# M220pal.net
KiCad netlist of a schematic drawn in EAGLE
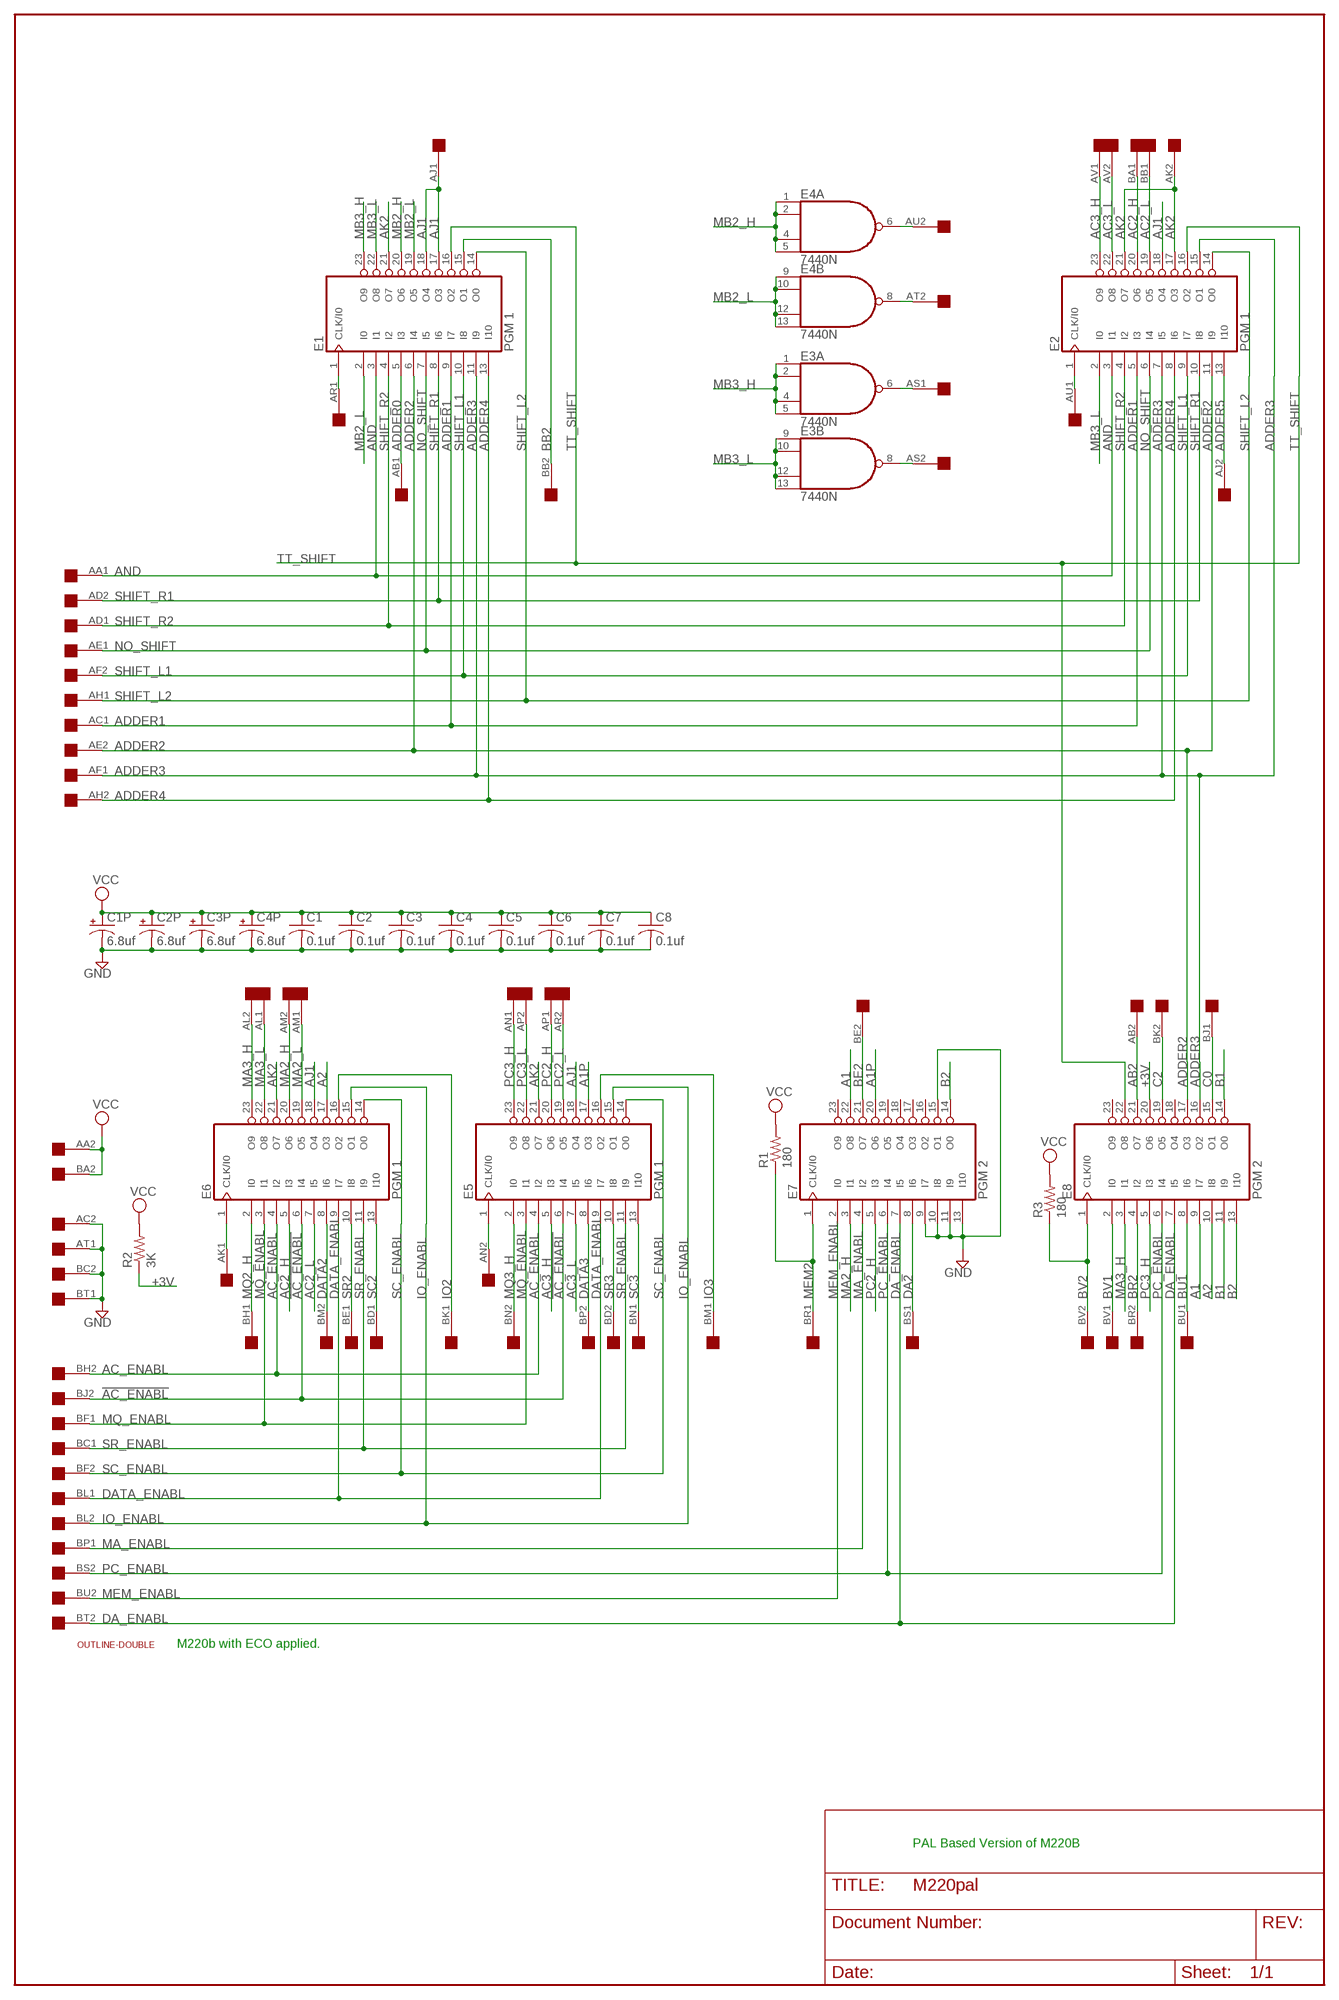
[diagram p0: schematic, sheet 1]

(export (version "E")
  (design (tool "Eeschema 10.0.6"))
  (components
    (comp (ref "C1")
      (value "0.1uf")
      (footprint "eagle-import:C050-025X075")
      (libsource (lib "eagle-import") (part "C-US050-025X075"))
    )
    (comp (ref "C1P")
      (value "6.8uf")
      (footprint "eagle-import:E15-5")
      (libsource (lib "eagle-import") (part "CPOL-USE15-5AXIAL"))
    )
    (comp (ref "C2")
      (value "0.1uf")
      (footprint "eagle-import:C050-025X075")
      (libsource (lib "eagle-import") (part "C-US050-025X075"))
    )
    (comp (ref "C2P")
      (value "6.8uf")
      (footprint "eagle-import:E15-5")
      (libsource (lib "eagle-import") (part "CPOL-USE15-5AXIAL"))
    )
    (comp (ref "C3")
      (value "0.1uf")
      (footprint "eagle-import:C050-025X075")
      (libsource (lib "eagle-import") (part "C-US050-025X075"))
    )
    (comp (ref "C3P")
      (value "6.8uf")
      (footprint "eagle-import:E15-5")
      (libsource (lib "eagle-import") (part "CPOL-USE15-5AXIAL"))
    )
    (comp (ref "C4")
      (value "0.1uf")
      (footprint "eagle-import:C050-025X075")
      (libsource (lib "eagle-import") (part "C-US050-025X075"))
    )
    (comp (ref "C4P")
      (value "6.8uf")
      (footprint "eagle-import:E15-5")
      (libsource (lib "eagle-import") (part "CPOL-USE15-5AXIAL"))
    )
    (comp (ref "C5")
      (value "0.1uf")
      (footprint "eagle-import:C050-025X075")
      (libsource (lib "eagle-import") (part "C-US050-025X075"))
    )
    (comp (ref "C6")
      (value "0.1uf")
      (footprint "eagle-import:C050-025X075")
      (libsource (lib "eagle-import") (part "C-US050-025X075"))
    )
    (comp (ref "C7")
      (value "0.1uf")
      (footprint "eagle-import:C050-025X075")
      (libsource (lib "eagle-import") (part "C-US050-025X075"))
    )
    (comp (ref "C8")
      (value "0.1uf")
      (footprint "eagle-import:C050-025X075")
      (libsource (lib "eagle-import") (part "C-US050-025X075"))
    )
    (comp (ref "E1")
      (value "PGM 1")
      (footprint "eagle-import:DIL24-3")
      (fields (field (name "MPN") "GAL22V10D-7LPN"))
      (libsource (lib "eagle-import") (part "22V10"))
    )
    (comp (ref "E2")
      (value "PGM 1")
      (footprint "eagle-import:DIL24-3")
      (fields (field (name "MPN") "GAL22V10D-7LPN"))
      (libsource (lib "eagle-import") (part "22V10"))
    )
    (comp (ref "E3")
      (value "7440N")
      (footprint "eagle-import:DIL14")
      (libsource (lib "eagle-import") (part "7420NS"))
    )
    (comp (ref "E4")
      (value "7440N")
      (footprint "eagle-import:DIL14")
      (libsource (lib "eagle-import") (part "7420NS"))
    )
    (comp (ref "E5")
      (value "PGM 1")
      (footprint "eagle-import:DIL24-3")
      (fields (field (name "MPN") "GAL22V10D-7LPN"))
      (libsource (lib "eagle-import") (part "22V10"))
    )
    (comp (ref "E6")
      (value "PGM 1")
      (footprint "eagle-import:DIL24-3")
      (fields (field (name "MPN") "GAL22V10D-7LPN"))
      (libsource (lib "eagle-import") (part "22V10"))
    )
    (comp (ref "E7")
      (value "PGM 2")
      (footprint "eagle-import:DIL24-3")
      (fields (field (name "MPN") "GAL22V10D-7LPN"))
      (libsource (lib "eagle-import") (part "22V10"))
    )
    (comp (ref "E8")
      (value "PGM 2")
      (footprint "eagle-import:DIL24-3")
      (fields (field (name "MPN") "GAL22V10D-7LPN"))
      (libsource (lib "eagle-import") (part "22V10"))
    )
    (comp (ref "R1")
      (value "180")
      (footprint "eagle-import:0207_10")
      (libsource (lib "eagle-import") (part "R-US_0207/10"))
    )
    (comp (ref "R2")
      (value "3K")
      (footprint "eagle-import:0207_10")
      (libsource (lib "eagle-import") (part "R-US_0207/10"))
    )
    (comp (ref "R3")
      (value "180")
      (footprint "eagle-import:0207_10")
      (libsource (lib "eagle-import") (part "R-US_0207/10"))
    )
    (comp (ref "U$1")
      (value "DOUBLE")
      (footprint "eagle-import:EDGE-CON4")
      (libsource (lib "eagle-import") (part "DOUBLE"))
    )
    (comp (ref "U$2")
      (value "OUTLINE-DOUBLE")
      (footprint "eagle-import:DOUBLE")
      (libsource (lib "eagle-import") (part "OUTLINE-DOUBLE"))
    )
  )
  (nets
    (net (code "1") (name "/+3V") (class "Default")
      (node (ref "E8") (pin "20") (pinfunction "O6_20") (pintype "bidirectional"))
      (node (ref "R2") (pin "1") (pinfunction "1_1") (pintype "passive"))
    )
    (net (code "2") (name "/A1") (class "Default")
      (node (ref "E7") (pin "22") (pinfunction "O8_22") (pintype "bidirectional"))
      (node (ref "E8") (pin "9") (pinfunction "I7_9") (pintype "input"))
    )
    (net (code "3") (name "/A1P") (class "Default")
      (node (ref "E5") (pin "17") (pinfunction "O3_17") (pintype "bidirectional"))
      (node (ref "E7") (pin "20") (pinfunction "O6_20") (pintype "bidirectional"))
    )
    (net (code "4") (name "/A2") (class "Default")
      (node (ref "E6") (pin "17") (pinfunction "O3_17") (pintype "bidirectional"))
      (node (ref "E8") (pin "10") (pinfunction "I8_10") (pintype "input"))
    )
    (net (code "5") (name "/AB2") (class "Default")
      (node (ref "E8") (pin "21") (pinfunction "O7_21") (pintype "bidirectional"))
      (node (ref "U$1") (pin "AB2") (pinfunction "1_AB2") (pintype "bidirectional"))
    )
    (net (code "6") (name "/AC2_H") (class "Default")
      (node (ref "E2") (pin "20") (pinfunction "O6_20") (pintype "bidirectional"))
      (node (ref "E6") (pin "5") (pinfunction "I3_5") (pintype "input"))
      (node (ref "U$1") (pin "BA1") (pinfunction "1_BA1") (pintype "bidirectional"))
    )
    (net (code "7") (name "/AC2_L") (class "Default")
      (node (ref "E2") (pin "19") (pinfunction "O5_19") (pintype "bidirectional"))
      (node (ref "E6") (pin "7") (pinfunction "I5_7") (pintype "input"))
      (node (ref "U$1") (pin "BB1") (pinfunction "1_BB1") (pintype "bidirectional"))
    )
    (net (code "8") (name "/AC3_H") (class "Default")
      (node (ref "E2") (pin "23") (pinfunction "O9_23") (pintype "bidirectional"))
      (node (ref "E5") (pin "5") (pinfunction "I3_5") (pintype "input"))
      (node (ref "U$1") (pin "AV1") (pinfunction "1_AV1") (pintype "bidirectional"))
    )
    (net (code "9") (name "/AC3_L") (class "Default")
      (node (ref "E2") (pin "22") (pinfunction "O8_22") (pintype "bidirectional"))
      (node (ref "E5") (pin "7") (pinfunction "I5_7") (pintype "input"))
      (node (ref "U$1") (pin "AV2") (pinfunction "1_AV2") (pintype "bidirectional"))
    )
    (net (code "10") (name "/AC_ENABL") (class "Default")
      (node (ref "E5") (pin "4") (pinfunction "I2_4") (pintype "input"))
      (node (ref "E6") (pin "4") (pinfunction "I2_4") (pintype "input"))
      (node (ref "U$1") (pin "BH2") (pinfunction "1_BH2") (pintype "bidirectional"))
    )
    (net (code "11") (name "/ADDER0") (class "Default")
      (node (ref "E1") (pin "5") (pinfunction "I3_5") (pintype "input"))
      (node (ref "U$1") (pin "AB1") (pinfunction "1_AB1") (pintype "bidirectional"))
    )
    (net (code "12") (name "/ADDER1") (class "Default")
      (node (ref "E1") (pin "9") (pinfunction "I7_9") (pintype "input"))
      (node (ref "E2") (pin "5") (pinfunction "I3_5") (pintype "input"))
      (node (ref "U$1") (pin "AC1") (pinfunction "1_AC1") (pintype "bidirectional"))
    )
    (net (code "13") (name "/ADDER2") (class "Default")
      (node (ref "E1") (pin "6") (pinfunction "I4_6") (pintype "input"))
      (node (ref "E2") (pin "11") (pinfunction "I9_11") (pintype "input"))
      (node (ref "E8") (pin "17") (pinfunction "O3_17") (pintype "bidirectional"))
      (node (ref "U$1") (pin "AE2") (pinfunction "1_AE2") (pintype "bidirectional"))
    )
    (net (code "14") (name "/ADDER3") (class "Default")
      (node (ref "E1") (pin "11") (pinfunction "I9_11") (pintype "input"))
      (node (ref "E2") (pin "15") (pinfunction "O1_15") (pintype "bidirectional"))
      (node (ref "E2") (pin "7") (pinfunction "I5_7") (pintype "input"))
      (node (ref "E8") (pin "16") (pinfunction "O2_16") (pintype "bidirectional"))
      (node (ref "U$1") (pin "AF1") (pinfunction "1_AF1") (pintype "bidirectional"))
    )
    (net (code "15") (name "/ADDER4") (class "Default")
      (node (ref "E1") (pin "13") (pinfunction "I10_13") (pintype "input"))
      (node (ref "E2") (pin "8") (pinfunction "I6_8") (pintype "input"))
      (node (ref "U$1") (pin "AH2") (pinfunction "1_AH2") (pintype "bidirectional"))
    )
    (net (code "16") (name "/ADDER5") (class "Default")
      (node (ref "E2") (pin "13") (pinfunction "I10_13") (pintype "input"))
      (node (ref "U$1") (pin "AJ2") (pinfunction "1_AJ2") (pintype "bidirectional"))
    )
    (net (code "17") (name "/AJ1") (class "Default")
      (node (ref "E1") (pin "17") (pinfunction "O3_17") (pintype "bidirectional"))
      (node (ref "E1") (pin "18") (pinfunction "O4_18") (pintype "bidirectional"))
      (node (ref "E2") (pin "18") (pinfunction "O4_18") (pintype "bidirectional"))
      (node (ref "E5") (pin "18") (pinfunction "O4_18") (pintype "bidirectional"))
      (node (ref "E6") (pin "18") (pinfunction "O4_18") (pintype "bidirectional"))
      (node (ref "U$1") (pin "AJ1") (pinfunction "1_AJ1") (pintype "bidirectional"))
    )
    (net (code "18") (name "/AK2") (class "Default")
      (node (ref "E1") (pin "21") (pinfunction "O7_21") (pintype "bidirectional"))
      (node (ref "E2") (pin "17") (pinfunction "O3_17") (pintype "bidirectional"))
      (node (ref "E2") (pin "21") (pinfunction "O7_21") (pintype "bidirectional"))
      (node (ref "E5") (pin "21") (pinfunction "O7_21") (pintype "bidirectional"))
      (node (ref "E6") (pin "21") (pinfunction "O7_21") (pintype "bidirectional"))
      (node (ref "U$1") (pin "AK2") (pinfunction "1_AK2") (pintype "bidirectional"))
    )
    (net (code "19") (name "/AND") (class "Default")
      (node (ref "E1") (pin "3") (pinfunction "I1_3") (pintype "input"))
      (node (ref "E2") (pin "3") (pinfunction "I1_3") (pintype "input"))
      (node (ref "U$1") (pin "AA1") (pinfunction "1_AA1") (pintype "bidirectional"))
    )
    (net (code "20") (name "/B1") (class "Default")
      (node (ref "E8") (pin "11") (pinfunction "I9_11") (pintype "input"))
      (node (ref "E8") (pin "14") (pinfunction "O0_14") (pintype "bidirectional"))
    )
    (net (code "21") (name "/B2") (class "Default")
      (node (ref "E7") (pin "14") (pinfunction "O0_14") (pintype "bidirectional"))
      (node (ref "E8") (pin "13") (pinfunction "I10_13") (pintype "input"))
    )
    (net (code "22") (name "/BB2") (class "Default")
      (node (ref "E1") (pin "15") (pinfunction "O1_15") (pintype "bidirectional"))
      (node (ref "U$1") (pin "BB2") (pinfunction "1_BB2") (pintype "bidirectional"))
    )
    (net (code "23") (name "/BE2") (class "Default")
      (node (ref "E7") (pin "21") (pinfunction "O7_21") (pintype "bidirectional"))
      (node (ref "U$1") (pin "BE2") (pinfunction "1_BE2") (pintype "bidirectional"))
    )
    (net (code "24") (name "/BR2") (class "Default")
      (node (ref "E8") (pin "4") (pinfunction "I2_4") (pintype "input"))
      (node (ref "U$1") (pin "BR2") (pinfunction "1_BR2") (pintype "bidirectional"))
    )
    (net (code "25") (name "/BU1") (class "Default")
      (node (ref "E8") (pin "8") (pinfunction "I6_8") (pintype "input"))
      (node (ref "U$1") (pin "BU1") (pinfunction "1_BU1") (pintype "bidirectional"))
    )
    (net (code "26") (name "/BV1") (class "Default")
      (node (ref "E8") (pin "2") (pinfunction "I0_2") (pintype "input"))
      (node (ref "U$1") (pin "BV1") (pinfunction "1_BV1") (pintype "bidirectional"))
    )
    (net (code "27") (name "/BV2") (class "Default")
      (node (ref "E8") (pin "1") (pinfunction "CLK/I0_1") (pintype "input"))
      (node (ref "R3") (pin "1") (pinfunction "1_1") (pintype "passive"))
      (node (ref "U$1") (pin "BV2") (pinfunction "1_BV2") (pintype "bidirectional"))
    )
    (net (code "28") (name "/C0") (class "Default")
      (node (ref "E8") (pin "15") (pinfunction "O1_15") (pintype "bidirectional"))
      (node (ref "U$1") (pin "BJ1") (pinfunction "1_BJ1") (pintype "bidirectional"))
    )
    (net (code "29") (name "/C2") (class "Default")
      (node (ref "E8") (pin "19") (pinfunction "O5_19") (pintype "bidirectional"))
      (node (ref "U$1") (pin "BK2") (pinfunction "1_BK2") (pintype "bidirectional"))
    )
    (net (code "30") (name "/DA2") (class "Default")
      (node (ref "E7") (pin "8") (pinfunction "I6_8") (pintype "input"))
      (node (ref "U$1") (pin "BS1") (pinfunction "1_BS1") (pintype "bidirectional"))
    )
    (net (code "31") (name "/DATA2") (class "Default")
      (node (ref "E6") (pin "8") (pinfunction "I6_8") (pintype "input"))
      (node (ref "U$1") (pin "BM2") (pinfunction "1_BM2") (pintype "bidirectional"))
    )
    (net (code "32") (name "/DATA3") (class "Default")
      (node (ref "E5") (pin "8") (pinfunction "I6_8") (pintype "input"))
      (node (ref "U$1") (pin "BP2") (pinfunction "1_BP2") (pintype "bidirectional"))
    )
    (net (code "33") (name "/DATA_ENABL") (class "Default")
      (node (ref "E5") (pin "9") (pinfunction "I7_9") (pintype "input"))
      (node (ref "E6") (pin "9") (pinfunction "I7_9") (pintype "input"))
      (node (ref "U$1") (pin "BL1") (pinfunction "1_BL1") (pintype "bidirectional"))
    )
    (net (code "34") (name "/DA_ENABL") (class "Default")
      (node (ref "E7") (pin "7") (pinfunction "I5_7") (pintype "input"))
      (node (ref "E8") (pin "7") (pinfunction "I5_7") (pintype "input"))
      (node (ref "U$1") (pin "BT2") (pinfunction "1_BT2") (pintype "bidirectional"))
    )
    (net (code "35") (name "/IO2") (class "Default")
      (node (ref "E6") (pin "16") (pinfunction "O2_16") (pintype "bidirectional"))
      (node (ref "U$1") (pin "BK1") (pinfunction "1_BK1") (pintype "bidirectional"))
    )
    (net (code "36") (name "/IO3") (class "Default")
      (node (ref "E5") (pin "16") (pinfunction "O2_16") (pintype "bidirectional"))
      (node (ref "U$1") (pin "BM1") (pinfunction "1_BM1") (pintype "bidirectional"))
    )
    (net (code "37") (name "/IO_ENABL") (class "Default")
      (node (ref "E5") (pin "15") (pinfunction "O1_15") (pintype "bidirectional"))
      (node (ref "E6") (pin "15") (pinfunction "O1_15") (pintype "bidirectional"))
      (node (ref "U$1") (pin "BL2") (pinfunction "1_BL2") (pintype "bidirectional"))
    )
    (net (code "38") (name "/MA2_H") (class "Default")
      (node (ref "E6") (pin "20") (pinfunction "O6_20") (pintype "bidirectional"))
      (node (ref "E7") (pin "3") (pinfunction "I1_3") (pintype "input"))
      (node (ref "U$1") (pin "AM2") (pinfunction "1_AM2") (pintype "bidirectional"))
    )
    (net (code "39") (name "/MA2_L") (class "Default")
      (node (ref "E6") (pin "19") (pinfunction "O5_19") (pintype "bidirectional"))
      (node (ref "U$1") (pin "AM1") (pinfunction "1_AM1") (pintype "bidirectional"))
    )
    (net (code "40") (name "/MA3_H") (class "Default")
      (node (ref "E6") (pin "23") (pinfunction "O9_23") (pintype "bidirectional"))
      (node (ref "E8") (pin "3") (pinfunction "I1_3") (pintype "input"))
      (node (ref "U$1") (pin "AL2") (pinfunction "1_AL2") (pintype "bidirectional"))
    )
    (net (code "41") (name "/MA3_L") (class "Default")
      (node (ref "E6") (pin "22") (pinfunction "O8_22") (pintype "bidirectional"))
      (node (ref "U$1") (pin "AL1") (pinfunction "1_AL1") (pintype "bidirectional"))
    )
    (net (code "42") (name "/MA_ENABL") (class "Default")
      (node (ref "E7") (pin "4") (pinfunction "I2_4") (pintype "input"))
      (node (ref "U$1") (pin "BP1") (pinfunction "1_BP1") (pintype "bidirectional"))
    )
    (net (code "43") (name "/MB2_H") (class "Default")
      (node (ref "E1") (pin "20") (pinfunction "O6_20") (pintype "bidirectional"))
      (node (ref "E4") (pin "1") (pinfunction "I0_1") (pintype "input"))
      (node (ref "E4") (pin "2") (pinfunction "I1_2") (pintype "input"))
      (node (ref "E4") (pin "4") (pinfunction "I2_4") (pintype "input"))
      (node (ref "E4") (pin "5") (pinfunction "I3_5") (pintype "input"))
    )
    (net (code "44") (name "/MB2_L") (class "Default")
      (node (ref "E1") (pin "19") (pinfunction "O5_19") (pintype "bidirectional"))
      (node (ref "E1") (pin "2") (pinfunction "I0_2") (pintype "input"))
      (node (ref "E4") (pin "10") (pinfunction "I1_10") (pintype "input"))
      (node (ref "E4") (pin "12") (pinfunction "I2_12") (pintype "input"))
      (node (ref "E4") (pin "13") (pinfunction "I3_13") (pintype "input"))
      (node (ref "E4") (pin "9") (pinfunction "I0_9") (pintype "input"))
    )
    (net (code "45") (name "/MB3_H") (class "Default")
      (node (ref "E1") (pin "23") (pinfunction "O9_23") (pintype "bidirectional"))
      (node (ref "E3") (pin "1") (pinfunction "I0_1") (pintype "input"))
      (node (ref "E3") (pin "2") (pinfunction "I1_2") (pintype "input"))
      (node (ref "E3") (pin "4") (pinfunction "I2_4") (pintype "input"))
      (node (ref "E3") (pin "5") (pinfunction "I3_5") (pintype "input"))
    )
    (net (code "46") (name "/MB3_L") (class "Default")
      (node (ref "E1") (pin "22") (pinfunction "O8_22") (pintype "bidirectional"))
      (node (ref "E2") (pin "2") (pinfunction "I0_2") (pintype "input"))
      (node (ref "E3") (pin "10") (pinfunction "I1_10") (pintype "input"))
      (node (ref "E3") (pin "12") (pinfunction "I2_12") (pintype "input"))
      (node (ref "E3") (pin "13") (pinfunction "I3_13") (pintype "input"))
      (node (ref "E3") (pin "9") (pinfunction "I0_9") (pintype "input"))
    )
    (net (code "47") (name "/MEM2") (class "Default")
      (node (ref "E7") (pin "1") (pinfunction "CLK/I0_1") (pintype "input"))
      (node (ref "R1") (pin "1") (pinfunction "1_1") (pintype "passive"))
      (node (ref "U$1") (pin "BR1") (pinfunction "1_BR1") (pintype "bidirectional"))
    )
    (net (code "48") (name "/MEM_ENABL") (class "Default")
      (node (ref "E7") (pin "2") (pinfunction "I0_2") (pintype "input"))
      (node (ref "U$1") (pin "BU2") (pinfunction "1_BU2") (pintype "bidirectional"))
    )
    (net (code "49") (name "/MQ2_H") (class "Default")
      (node (ref "E6") (pin "2") (pinfunction "I0_2") (pintype "input"))
      (node (ref "U$1") (pin "BH1") (pinfunction "1_BH1") (pintype "bidirectional"))
    )
    (net (code "50") (name "/MQ3_H") (class "Default")
      (node (ref "E5") (pin "2") (pinfunction "I0_2") (pintype "input"))
      (node (ref "U$1") (pin "BN2") (pinfunction "1_BN2") (pintype "bidirectional"))
    )
    (net (code "51") (name "/MQ_ENABL") (class "Default")
      (node (ref "E5") (pin "3") (pinfunction "I1_3") (pintype "input"))
      (node (ref "E6") (pin "3") (pinfunction "I1_3") (pintype "input"))
      (node (ref "U$1") (pin "BF1") (pinfunction "1_BF1") (pintype "bidirectional"))
    )
    (net (code "52") (name "/NO_SHIFT") (class "Default")
      (node (ref "E1") (pin "7") (pinfunction "I5_7") (pintype "input"))
      (node (ref "E2") (pin "6") (pinfunction "I4_6") (pintype "input"))
      (node (ref "U$1") (pin "AE1") (pinfunction "1_AE1") (pintype "bidirectional"))
    )
    (net (code "53") (name "/PC2_H") (class "Default")
      (node (ref "E5") (pin "20") (pinfunction "O6_20") (pintype "bidirectional"))
      (node (ref "E7") (pin "5") (pinfunction "I3_5") (pintype "input"))
      (node (ref "U$1") (pin "AP1") (pinfunction "1_AP1") (pintype "bidirectional"))
    )
    (net (code "54") (name "/PC2_L") (class "Default")
      (node (ref "E5") (pin "19") (pinfunction "O5_19") (pintype "bidirectional"))
      (node (ref "U$1") (pin "AR2") (pinfunction "1_AR2") (pintype "bidirectional"))
    )
    (net (code "55") (name "/PC3_H") (class "Default")
      (node (ref "E5") (pin "23") (pinfunction "O9_23") (pintype "bidirectional"))
      (node (ref "E8") (pin "5") (pinfunction "I3_5") (pintype "input"))
      (node (ref "U$1") (pin "AN1") (pinfunction "1_AN1") (pintype "bidirectional"))
    )
    (net (code "56") (name "/PC3_L") (class "Default")
      (node (ref "E5") (pin "22") (pinfunction "O8_22") (pintype "bidirectional"))
      (node (ref "U$1") (pin "AP2") (pinfunction "1_AP2") (pintype "bidirectional"))
    )
    (net (code "57") (name "/PC_ENABL") (class "Default")
      (node (ref "E7") (pin "6") (pinfunction "I4_6") (pintype "input"))
      (node (ref "E8") (pin "6") (pinfunction "I4_6") (pintype "input"))
      (node (ref "U$1") (pin "BS2") (pinfunction "1_BS2") (pintype "bidirectional"))
    )
    (net (code "58") (name "/SC2") (class "Default")
      (node (ref "E6") (pin "13") (pinfunction "I10_13") (pintype "input"))
      (node (ref "U$1") (pin "BD1") (pinfunction "1_BD1") (pintype "bidirectional"))
    )
    (net (code "59") (name "/SC3") (class "Default")
      (node (ref "E5") (pin "13") (pinfunction "I10_13") (pintype "input"))
      (node (ref "U$1") (pin "BN1") (pinfunction "1_BN1") (pintype "bidirectional"))
    )
    (net (code "60") (name "/SC_ENABL") (class "Default")
      (node (ref "E5") (pin "14") (pinfunction "O0_14") (pintype "bidirectional"))
      (node (ref "E6") (pin "14") (pinfunction "O0_14") (pintype "bidirectional"))
      (node (ref "U$1") (pin "BF2") (pinfunction "1_BF2") (pintype "bidirectional"))
    )
    (net (code "61") (name "/SHIFT_L1") (class "Default")
      (node (ref "E1") (pin "10") (pinfunction "I8_10") (pintype "input"))
      (node (ref "E2") (pin "9") (pinfunction "I7_9") (pintype "input"))
      (node (ref "U$1") (pin "AF2") (pinfunction "1_AF2") (pintype "bidirectional"))
    )
    (net (code "62") (name "/SHIFT_L2") (class "Default")
      (node (ref "E1") (pin "14") (pinfunction "O0_14") (pintype "bidirectional"))
      (node (ref "E2") (pin "14") (pinfunction "O0_14") (pintype "bidirectional"))
      (node (ref "U$1") (pin "AH1") (pinfunction "1_AH1") (pintype "bidirectional"))
    )
    (net (code "63") (name "/SHIFT_R1") (class "Default")
      (node (ref "E1") (pin "8") (pinfunction "I6_8") (pintype "input"))
      (node (ref "E2") (pin "10") (pinfunction "I8_10") (pintype "input"))
      (node (ref "U$1") (pin "AD2") (pinfunction "1_AD2") (pintype "bidirectional"))
    )
    (net (code "64") (name "/SHIFT_R2") (class "Default")
      (node (ref "E1") (pin "4") (pinfunction "I2_4") (pintype "input"))
      (node (ref "E2") (pin "4") (pinfunction "I2_4") (pintype "input"))
      (node (ref "U$1") (pin "AD1") (pinfunction "1_AD1") (pintype "bidirectional"))
    )
    (net (code "65") (name "/SR2") (class "Default")
      (node (ref "E6") (pin "10") (pinfunction "I8_10") (pintype "input"))
      (node (ref "U$1") (pin "BE1") (pinfunction "1_BE1") (pintype "bidirectional"))
    )
    (net (code "66") (name "/SR3") (class "Default")
      (node (ref "E5") (pin "10") (pinfunction "I8_10") (pintype "input"))
      (node (ref "U$1") (pin "BD2") (pinfunction "1_BD2") (pintype "bidirectional"))
    )
    (net (code "67") (name "/SR_ENABL") (class "Default")
      (node (ref "E5") (pin "11") (pinfunction "I9_11") (pintype "input"))
      (node (ref "E6") (pin "11") (pinfunction "I9_11") (pintype "input"))
      (node (ref "U$1") (pin "BC1") (pinfunction "1_BC1") (pintype "bidirectional"))
    )
    (net (code "68") (name "/TT_SHIFT") (class "Default")
      (node (ref "E1") (pin "16") (pinfunction "O2_16") (pintype "bidirectional"))
      (node (ref "E2") (pin "16") (pinfunction "O2_16") (pintype "bidirectional"))
      (node (ref "E8") (pin "22") (pinfunction "O8_22") (pintype "bidirectional"))
    )
    (net (code "69") (name "/~{AC_ENABL}") (class "Default")
      (node (ref "E5") (pin "6") (pinfunction "I4_6") (pintype "input"))
      (node (ref "E6") (pin "6") (pinfunction "I4_6") (pintype "input"))
      (node (ref "U$1") (pin "BJ2") (pinfunction "1_BJ2") (pintype "bidirectional"))
    )
    (net (code "70") (name "GND") (class "Default")
      (node (ref "C1") (pin "2") (pinfunction "2_2") (pintype "passive"))
      (node (ref "C1P") (pin "-") (pinfunction "-_-") (pintype "passive"))
      (node (ref "C2") (pin "2") (pinfunction "2_2") (pintype "passive"))
      (node (ref "C2P") (pin "-") (pinfunction "-_-") (pintype "passive"))
      (node (ref "C3") (pin "2") (pinfunction "2_2") (pintype "passive"))
      (node (ref "C3P") (pin "-") (pinfunction "-_-") (pintype "passive"))
      (node (ref "C4") (pin "2") (pinfunction "2_2") (pintype "passive"))
      (node (ref "C4P") (pin "-") (pinfunction "-_-") (pintype "passive"))
      (node (ref "C5") (pin "2") (pinfunction "2_2") (pintype "passive"))
      (node (ref "C6") (pin "2") (pinfunction "2_2") (pintype "passive"))
      (node (ref "C7") (pin "2") (pinfunction "2_2") (pintype "passive"))
      (node (ref "C8") (pin "2") (pinfunction "2_2") (pintype "passive"))
      (node (ref "E7") (pin "10") (pinfunction "I8_10") (pintype "input"))
      (node (ref "E7") (pin "11") (pinfunction "I9_11") (pintype "input"))
      (node (ref "E7") (pin "13") (pinfunction "I10_13") (pintype "input"))
      (node (ref "E7") (pin "15") (pinfunction "O1_15") (pintype "bidirectional"))
      (node (ref "E7") (pin "9") (pinfunction "I7_9") (pintype "input"))
      (node (ref "U$1") (pin "AC2") (pinfunction "1_AC2") (pintype "bidirectional"))
      (node (ref "U$1") (pin "AT1") (pinfunction "1_AT1") (pintype "bidirectional"))
      (node (ref "U$1") (pin "BC2") (pinfunction "1_BC2") (pintype "bidirectional"))
      (node (ref "U$1") (pin "BT1") (pinfunction "1_BT1") (pintype "bidirectional"))
    )
    (net (code "71") (name "Net-(E1A-CLK{slash}I0)") (class "Default")
      (node (ref "E1") (pin "1") (pinfunction "CLK/I0_1") (pintype "input"))
      (node (ref "U$1") (pin "AR1") (pinfunction "1_AR1") (pintype "bidirectional"))
    )
    (net (code "72") (name "Net-(E2A-CLK{slash}I0)") (class "Default")
      (node (ref "E2") (pin "1") (pinfunction "CLK/I0_1") (pintype "input"))
      (node (ref "U$1") (pin "AU1") (pinfunction "1_AU1") (pintype "bidirectional"))
    )
    (net (code "73") (name "Net-(E3A-O)") (class "Default")
      (node (ref "E3") (pin "6") (pinfunction "O_6") (pintype "output"))
      (node (ref "U$1") (pin "AS1") (pinfunction "1_AS1") (pintype "bidirectional"))
    )
    (net (code "74") (name "Net-(E3B-O)") (class "Default")
      (node (ref "E3") (pin "8") (pinfunction "O_8") (pintype "output"))
      (node (ref "U$1") (pin "AS2") (pinfunction "1_AS2") (pintype "bidirectional"))
    )
    (net (code "75") (name "Net-(E4A-O)") (class "Default")
      (node (ref "E4") (pin "6") (pinfunction "O_6") (pintype "output"))
      (node (ref "U$1") (pin "AU2") (pinfunction "1_AU2") (pintype "bidirectional"))
    )
    (net (code "76") (name "Net-(E4B-O)") (class "Default")
      (node (ref "E4") (pin "8") (pinfunction "O_8") (pintype "output"))
      (node (ref "U$1") (pin "AT2") (pinfunction "1_AT2") (pintype "bidirectional"))
    )
    (net (code "77") (name "Net-(E5A-CLK{slash}I0)") (class "Default")
      (node (ref "E5") (pin "1") (pinfunction "CLK/I0_1") (pintype "input"))
      (node (ref "U$1") (pin "AN2") (pinfunction "1_AN2") (pintype "bidirectional"))
    )
    (net (code "78") (name "Net-(E6A-CLK{slash}I0)") (class "Default")
      (node (ref "E6") (pin "1") (pinfunction "CLK/I0_1") (pintype "input"))
      (node (ref "U$1") (pin "AK1") (pinfunction "1_AK1") (pintype "bidirectional"))
    )
    (net (code "79") (name "VCC") (class "Default")
      (node (ref "C1") (pin "1") (pinfunction "1_1") (pintype "passive"))
      (node (ref "C1P") (pin "+") (pinfunction "+_+") (pintype "passive"))
      (node (ref "C2") (pin "1") (pinfunction "1_1") (pintype "passive"))
      (node (ref "C2P") (pin "+") (pinfunction "+_+") (pintype "passive"))
      (node (ref "C3") (pin "1") (pinfunction "1_1") (pintype "passive"))
      (node (ref "C3P") (pin "+") (pinfunction "+_+") (pintype "passive"))
      (node (ref "C4") (pin "1") (pinfunction "1_1") (pintype "passive"))
      (node (ref "C4P") (pin "+") (pinfunction "+_+") (pintype "passive"))
      (node (ref "C5") (pin "1") (pinfunction "1_1") (pintype "passive"))
      (node (ref "C6") (pin "1") (pinfunction "1_1") (pintype "passive"))
      (node (ref "C7") (pin "1") (pinfunction "1_1") (pintype "passive"))
      (node (ref "C8") (pin "1") (pinfunction "1_1") (pintype "passive"))
      (node (ref "R1") (pin "2") (pinfunction "2_2") (pintype "passive"))
      (node (ref "R2") (pin "2") (pinfunction "2_2") (pintype "passive"))
      (node (ref "R3") (pin "2") (pinfunction "2_2") (pintype "passive"))
      (node (ref "U$1") (pin "AA2") (pinfunction "1_AA2") (pintype "bidirectional"))
      (node (ref "U$1") (pin "BA2") (pinfunction "1_BA2") (pintype "bidirectional"))
    )
    (net (code "80") (name "unconnected-(E7A-O2-Pad16)") (class "Default")
      (node (ref "E7") (pin "16") (pinfunction "O2_16") (pintype "bidirectional"))
    )
    (net (code "81") (name "unconnected-(E7A-O3-Pad17)") (class "Default")
      (node (ref "E7") (pin "17") (pinfunction "O3_17") (pintype "bidirectional"))
    )
    (net (code "82") (name "unconnected-(E7A-O4-Pad18)") (class "Default")
      (node (ref "E7") (pin "18") (pinfunction "O4_18") (pintype "bidirectional"))
    )
    (net (code "83") (name "unconnected-(E7A-O5-Pad19)") (class "Default")
      (node (ref "E7") (pin "19") (pinfunction "O5_19") (pintype "bidirectional"))
    )
    (net (code "84") (name "unconnected-(E7A-O9-Pad23)") (class "Default")
      (node (ref "E7") (pin "23") (pinfunction "O9_23") (pintype "bidirectional"))
    )
    (net (code "85") (name "unconnected-(E8A-O4-Pad18)") (class "Default")
      (node (ref "E8") (pin "18") (pinfunction "O4_18") (pintype "bidirectional"))
    )
    (net (code "86") (name "unconnected-(E8A-O9-Pad23)") (class "Default")
      (node (ref "E8") (pin "23") (pinfunction "O9_23") (pintype "bidirectional"))
    )
  )
)
